# tmtr_board_rev1_0.net
KiCad netlist of a schematic drawn in Altium Designer
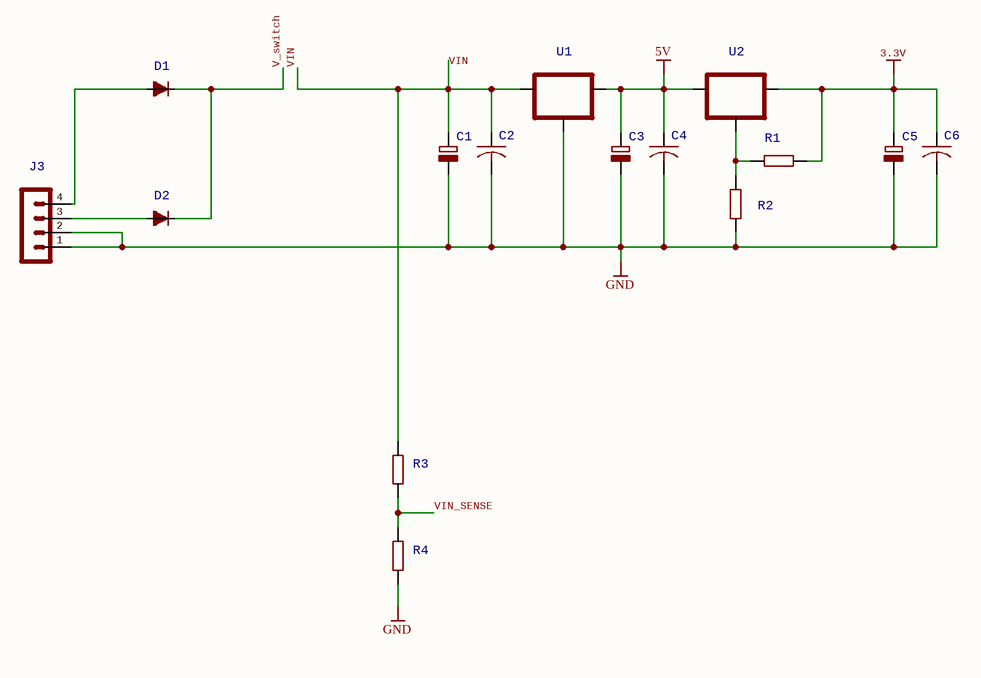
[diagram p0: tmtr_board_rev1_0.SchDoc]

(export (version "E")
  (design (tool "Eeschema 10.0.6"))
  (components
    (comp (ref "C1")
      (value "<B>POLARIZED CAPACITOR</B>, European symbol")
      (footprint "153CLV-0810")
      (libsource (lib "rcl") (part "CPOL-EU153CLV-0810"))
    )
    (comp (ref "C2")
      (value "<B>CAPACITOR</B>, American symbol")
      (footprint "C0805K")
      (libsource (lib "rcl") (part "C-USC0805K"))
    )
    (comp (ref "C3")
      (value "<B>POLARIZED CAPACITOR</B>, European symbol")
      (footprint "153CLV-0810")
      (libsource (lib "rcl") (part "CPOL-EU153CLV-0810"))
    )
    (comp (ref "C4")
      (value "<B>CAPACITOR</B>, American symbol")
      (footprint "C0805K")
      (libsource (lib "rcl") (part "C-USC0805K"))
    )
    (comp (ref "C5")
      (value "<B>POLARIZED CAPACITOR</B>, European symbol")
      (footprint "153CLV-0810")
      (libsource (lib "rcl") (part "CPOL-EU153CLV-0810"))
    )
    (comp (ref "C6")
      (value "<B>CAPACITOR</B>, American symbol")
      (footprint "C0805K")
      (libsource (lib "rcl") (part "C-USC0805K"))
    )
    (comp (ref "D1")
      (value "D-FILL-SMB")
      (footprint "SMB")
      (description "<B>DIODE</B><p>\nfilled")
      (libsource (lib "semicon-smd-ipc") (part "D-FILL-SMB"))
    )
    (comp (ref "D2")
      (value "D-FILL-SMB")
      (footprint "SMB")
      (description "<B>DIODE</B><p>\nfilled")
      (libsource (lib "semicon-smd-ipc") (part "D-FILL-SMB"))
    )
    (comp (ref "J3")
      (value "MA04-1")
      (footprint "MA04-1")
      (description "<b>PIN HEADER</b>")
      (libsource (lib "con-lstb") (part "MA04-1"))
    )
    (comp (ref "R1")
      (value "R-EU_M0805")
      (footprint "M0805")
      (description "<B>RESISTOR</B>, European symbol")
      (libsource (lib "resistor") (part "R-EU_M0805"))
    )
    (comp (ref "R2")
      (value "R-EU_M0805")
      (footprint "M0805")
      (description "<B>RESISTOR</B>, European symbol")
      (libsource (lib "resistor") (part "R-EU_M0805"))
    )
    (comp (ref "R3")
      (value "R-EU_M0805")
      (footprint "M0805")
      (description "<B>RESISTOR</B>, European symbol")
      (libsource (lib "resistor") (part "R-EU_M0805"))
    )
    (comp (ref "R4")
      (value "R-EU_M0805")
      (footprint "M0805")
      (description "<B>RESISTOR</B>, European symbol")
      (libsource (lib "resistor") (part "R-EU_M0805"))
    )
    (comp (ref "U1")
      (value "78XXS")
      (footprint "78XXS")
      (description "<b>VOLTAGE REGULATOR</b>")
      (libsource (lib "v-reg") (part "78XXS"))
    )
    (comp (ref "U2") (value "LD117A?*S") (footprint "SOT223") (libsource (lib "v-reg") (part "LD117A?*S")))
  )
  (nets
    (net (code "1") (name "/VIN") (class "Default")
      (node (ref "C1") (pin "+") (pinfunction "+_+") (pintype "passive"))
      (node (ref "C2") (pin "1") (pinfunction "1_1") (pintype "passive"))
      (node (ref "R3") (pin "1") (pinfunction "1_1") (pintype "passive"))
      (node (ref "U1") (pin "IN") (pinfunction "IN_IN") (pintype "passive"))
    )
    (net (code "2") (name "/VIN_SENSE") (class "Default")
      (node (ref "R3") (pin "2") (pinfunction "2_2") (pintype "passive"))
      (node (ref "R4") (pin "1") (pinfunction "1_1") (pintype "passive"))
    )
    (net (code "3") (name "/V_switch") (class "Default")
      (node (ref "D1") (pin "1") (pinfunction "C_1") (pintype "passive"))
      (node (ref "D2") (pin "1") (pinfunction "C_1") (pintype "passive"))
    )
    (net (code "4") (name "3.3V") (class "Default")
      (node (ref "C5") (pin "+") (pinfunction "+_+") (pintype "passive"))
      (node (ref "C6") (pin "1") (pinfunction "1_1") (pintype "passive"))
      (node (ref "R1") (pin "2") (pinfunction "2_2") (pintype "passive"))
      (node (ref "U2") (pin "4") (pinfunction "OUT_4") (pintype "passive"))
    )
    (net (code "5") (name "5V") (class "Default")
      (node (ref "C3") (pin "+") (pinfunction "+_+") (pintype "passive"))
      (node (ref "C4") (pin "1") (pinfunction "1_1") (pintype "passive"))
      (node (ref "U1") (pin "OUT") (pinfunction "OUT_OUT") (pintype "passive"))
      (node (ref "U2") (pin "3") (pinfunction "IN_3") (pintype "passive"))
    )
    (net (code "6") (name "GND") (class "Default")
      (node (ref "C1") (pin "-") (pinfunction "-_-") (pintype "passive"))
      (node (ref "C2") (pin "2") (pinfunction "2_2") (pintype "passive"))
      (node (ref "C3") (pin "-") (pinfunction "-_-") (pintype "passive"))
      (node (ref "C4") (pin "2") (pinfunction "2_2") (pintype "passive"))
      (node (ref "C5") (pin "-") (pinfunction "-_-") (pintype "passive"))
      (node (ref "C6") (pin "2") (pinfunction "2_2") (pintype "passive"))
      (node (ref "J3") (pin "1") (pinfunction "1_1") (pintype "passive"))
      (node (ref "J3") (pin "2") (pinfunction "2_2") (pintype "passive"))
      (node (ref "R2") (pin "2") (pinfunction "2_2") (pintype "passive"))
      (node (ref "R4") (pin "2") (pinfunction "2_2") (pintype "passive"))
      (node (ref "U1") (pin "GND") (pinfunction "GND_GND") (pintype "passive"))
    )
    (net (code "7") (name "Net-(D1-A)") (class "Default")
      (node (ref "D1") (pin "2") (pinfunction "A_2") (pintype "passive"))
      (node (ref "J3") (pin "4") (pinfunction "4_4") (pintype "passive"))
    )
    (net (code "8") (name "Net-(D2-A)") (class "Default")
      (node (ref "D2") (pin "2") (pinfunction "A_2") (pintype "passive"))
      (node (ref "J3") (pin "3") (pinfunction "3_3") (pintype "passive"))
    )
    (net (code "9") (name "Net-(U2-ADJ)") (class "Default")
      (node (ref "R1") (pin "1") (pinfunction "1_1") (pintype "passive"))
      (node (ref "R2") (pin "1") (pinfunction "1_1") (pintype "passive"))
      (node (ref "U2") (pin "1") (pinfunction "ADJ_1") (pintype "passive"))
    )
  )
)
